# PDM_no_main_relay.net
KiCad netlist of a schematic drawn in EAGLE
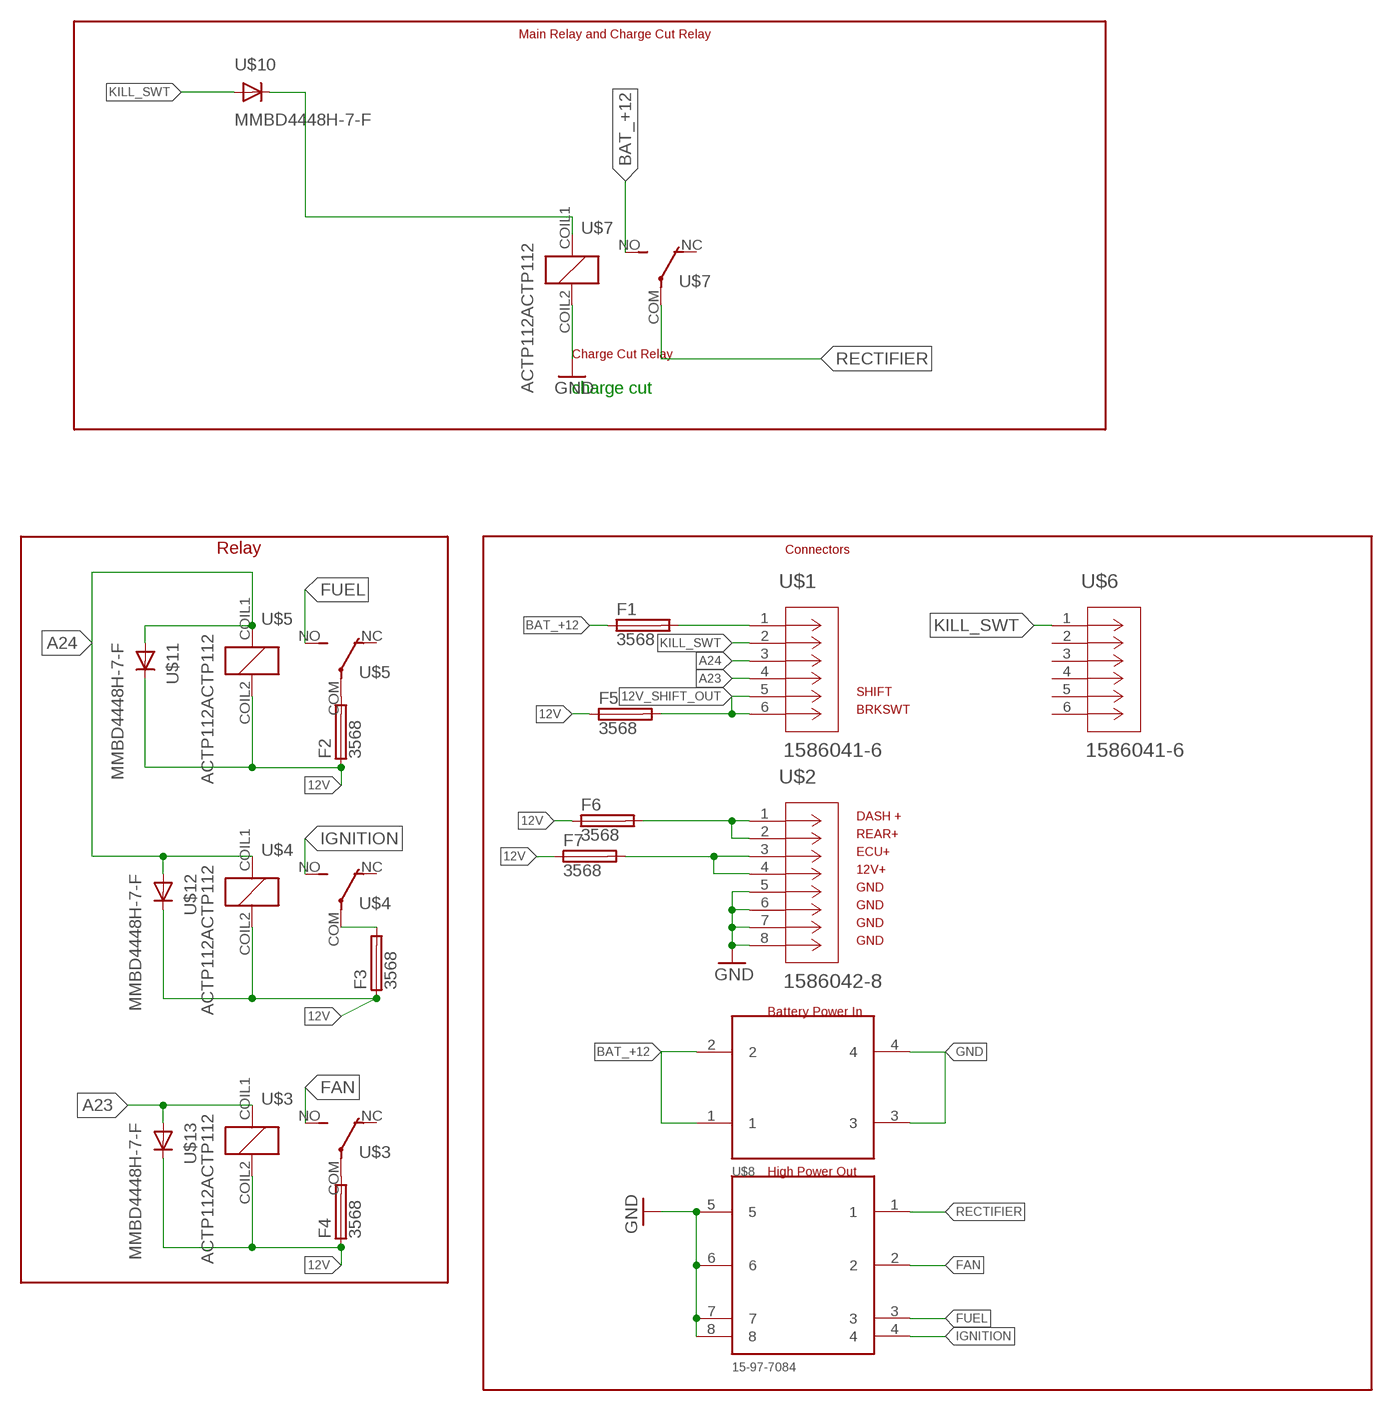
[diagram p0: schematic, sheet 1]

(export (version "E")
  (design (tool "Eeschema 10.0.6"))
  (components
    (comp (ref "F1")
      (value "3568")
      (footprint "eagle-import:3568")
      (libsource (lib "eagle-import") (part "3568"))
    )
    (comp (ref "F2")
      (value "3568")
      (footprint "eagle-import:3568")
      (libsource (lib "eagle-import") (part "3568"))
    )
    (comp (ref "F3")
      (value "3568")
      (footprint "eagle-import:3568")
      (libsource (lib "eagle-import") (part "3568"))
    )
    (comp (ref "F4")
      (value "3568")
      (footprint "eagle-import:3568")
      (libsource (lib "eagle-import") (part "3568"))
    )
    (comp (ref "F5")
      (value "3568")
      (footprint "eagle-import:3568")
      (libsource (lib "eagle-import") (part "3568"))
    )
    (comp (ref "F6")
      (value "3568")
      (footprint "eagle-import:3568")
      (libsource (lib "eagle-import") (part "3568"))
    )
    (comp (ref "F7")
      (value "3568")
      (footprint "eagle-import:3568")
      (libsource (lib "eagle-import") (part "3568"))
    )
    (comp (ref "U$1")
      (value "1586041-6")
      (footprint "eagle-import:1586041-6")
      (libsource (lib "eagle-import") (part "1586041-6"))
    )
    (comp (ref "U$2")
      (value "1586042-8")
      (footprint "eagle-import:1586042-8")
      (libsource (lib "eagle-import") (part "1586042-8"))
    )
    (comp (ref "U$3")
      (value "ACTP112ACTP112")
      (footprint "eagle-import:ACTP112")
      (libsource (lib "eagle-import") (part "ACTP112ACTP112"))
    )
    (comp (ref "U$4")
      (value "ACTP112ACTP112")
      (footprint "eagle-import:ACTP112")
      (libsource (lib "eagle-import") (part "ACTP112ACTP112"))
    )
    (comp (ref "U$5")
      (value "ACTP112ACTP112")
      (footprint "eagle-import:ACTP112")
      (libsource (lib "eagle-import") (part "ACTP112ACTP112"))
    )
    (comp (ref "U$6")
      (value "1586041-6")
      (footprint "eagle-import:1586041-6")
      (libsource (lib "eagle-import") (part "1586041-6"))
    )
    (comp (ref "U$7")
      (value "ACTP112ACTP112")
      (footprint "eagle-import:ACTP112")
      (libsource (lib "eagle-import") (part "ACTP112ACTP112"))
    )
    (comp (ref "U$8")
      (value "15-97-7084")
      (footprint "eagle-import:15-97-7084")
      (libsource (lib "eagle-import") (part "15-97-7084"))
    )
    (comp (ref "U$9")
      (value "15-97-8043")
      (footprint "eagle-import:15-97-8043")
      (libsource (lib "eagle-import") (part "15-97-8043"))
    )
    (comp (ref "U$10")
      (value "MMBD4448H-7-F")
      (footprint "eagle-import:SOT23-3")
      (libsource (lib "eagle-import") (part "MMBD4448H-7-F"))
    )
    (comp (ref "U$11")
      (value "MMBD4448H-7-F")
      (footprint "eagle-import:SOT23-3")
      (libsource (lib "eagle-import") (part "MMBD4448H-7-F"))
    )
    (comp (ref "U$12")
      (value "MMBD4448H-7-F")
      (footprint "eagle-import:SOT23-3")
      (libsource (lib "eagle-import") (part "MMBD4448H-7-F"))
    )
    (comp (ref "U$13")
      (value "MMBD4448H-7-F")
      (footprint "eagle-import:SOT23-3")
      (libsource (lib "eagle-import") (part "MMBD4448H-7-F"))
    )
  )
  (nets
    (net (code "1") (name "12V") (class "Default")
      (node (ref "F2") (pin "1") (pinfunction "1_1") (pintype "passive"))
      (node (ref "F2") (pin "2") (pinfunction "1_2") (pintype "passive"))
      (node (ref "F3") (pin "1") (pinfunction "1_1") (pintype "passive"))
      (node (ref "F3") (pin "2") (pinfunction "1_2") (pintype "passive"))
      (node (ref "F4") (pin "1") (pinfunction "1_1") (pintype "passive"))
      (node (ref "F4") (pin "2") (pinfunction "1_2") (pintype "passive"))
      (node (ref "F5") (pin "1") (pinfunction "1_1") (pintype "passive"))
      (node (ref "F5") (pin "2") (pinfunction "1_2") (pintype "passive"))
      (node (ref "F6") (pin "1") (pinfunction "1_1") (pintype "passive"))
      (node (ref "F6") (pin "2") (pinfunction "1_2") (pintype "passive"))
      (node (ref "F7") (pin "1") (pinfunction "1_1") (pintype "passive"))
      (node (ref "F7") (pin "2") (pinfunction "1_2") (pintype "passive"))
      (node (ref "U$11") (pin "3") (pinfunction "C_3") (pintype "passive"))
      (node (ref "U$12") (pin "3") (pinfunction "C_3") (pintype "passive"))
      (node (ref "U$13") (pin "3") (pinfunction "C_3") (pintype "passive"))
      (node (ref "U$3") (pin "COIL2") (pinfunction "COIL2_COIL2") (pintype "passive"))
      (node (ref "U$4") (pin "COIL2") (pinfunction "COIL2_COIL2") (pintype "passive"))
      (node (ref "U$5") (pin "COIL2") (pinfunction "COIL2_COIL2") (pintype "passive"))
    )
    (net (code "2") (name "12V_SHIFT_OUT") (class "Default")
      (node (ref "F5") (pin "3") (pinfunction "2_3") (pintype "passive"))
      (node (ref "F5") (pin "4") (pinfunction "2_4") (pintype "passive"))
      (node (ref "U$1") (pin "5") (pinfunction "5_5") (pintype "passive"))
      (node (ref "U$1") (pin "6") (pinfunction "6_6") (pintype "passive"))
    )
    (net (code "3") (name "A23") (class "Default")
      (node (ref "U$1") (pin "4") (pinfunction "4_4") (pintype "passive"))
      (node (ref "U$13") (pin "1") (pinfunction "A_1") (pintype "passive"))
      (node (ref "U$3") (pin "COIL1") (pinfunction "COIL1_COIL1") (pintype "passive"))
    )
    (net (code "4") (name "A24") (class "Default")
      (node (ref "U$1") (pin "3") (pinfunction "3_3") (pintype "passive"))
      (node (ref "U$11") (pin "1") (pinfunction "A_1") (pintype "passive"))
      (node (ref "U$12") (pin "1") (pinfunction "A_1") (pintype "passive"))
      (node (ref "U$4") (pin "COIL1") (pinfunction "COIL1_COIL1") (pintype "passive"))
      (node (ref "U$5") (pin "COIL1") (pinfunction "COIL1_COIL1") (pintype "passive"))
    )
    (net (code "5") (name "BAT_+12") (class "Default")
      (node (ref "F1") (pin "1") (pinfunction "1_1") (pintype "passive"))
      (node (ref "F1") (pin "2") (pinfunction "1_2") (pintype "passive"))
      (node (ref "U$7") (pin "NO") (pinfunction "NO_NO") (pintype "passive"))
      (node (ref "U$9") (pin "1") (pinfunction "1_1") (pintype "bidirectional"))
      (node (ref "U$9") (pin "2") (pinfunction "2_2") (pintype "bidirectional"))
    )
    (net (code "6") (name "FAN") (class "Default")
      (node (ref "U$3") (pin "NO") (pinfunction "NO_NO") (pintype "passive"))
      (node (ref "U$8") (pin "2") (pinfunction "2_2") (pintype "bidirectional"))
    )
    (net (code "7") (name "FUEL") (class "Default")
      (node (ref "U$5") (pin "NO") (pinfunction "NO_NO") (pintype "passive"))
      (node (ref "U$8") (pin "3") (pinfunction "3_3") (pintype "bidirectional"))
    )
    (net (code "8") (name "GND") (class "Default")
      (node (ref "U$2") (pin "5") (pinfunction "5_5") (pintype "passive"))
      (node (ref "U$2") (pin "6") (pinfunction "6_6") (pintype "passive"))
      (node (ref "U$2") (pin "7") (pinfunction "7_7") (pintype "passive"))
      (node (ref "U$2") (pin "8") (pinfunction "8_8") (pintype "passive"))
      (node (ref "U$7") (pin "COIL2") (pinfunction "COIL2_COIL2") (pintype "passive"))
      (node (ref "U$8") (pin "5") (pinfunction "5_5") (pintype "bidirectional"))
      (node (ref "U$8") (pin "6") (pinfunction "6_6") (pintype "bidirectional"))
      (node (ref "U$8") (pin "7") (pinfunction "7_7") (pintype "bidirectional"))
      (node (ref "U$8") (pin "8") (pinfunction "8_8") (pintype "bidirectional"))
      (node (ref "U$9") (pin "3") (pinfunction "3_3") (pintype "bidirectional"))
      (node (ref "U$9") (pin "4") (pinfunction "4_4") (pintype "bidirectional"))
    )
    (net (code "9") (name "IGNITION") (class "Default")
      (node (ref "U$4") (pin "NO") (pinfunction "NO_NO") (pintype "passive"))
      (node (ref "U$8") (pin "4") (pinfunction "4_4") (pintype "bidirectional"))
    )
    (net (code "10") (name "KILL_SWT") (class "Default")
      (node (ref "U$1") (pin "2") (pinfunction "2_2") (pintype "passive"))
      (node (ref "U$10") (pin "1") (pinfunction "A_1") (pintype "passive"))
      (node (ref "U$6") (pin "1") (pinfunction "1_1") (pintype "passive"))
    )
    (net (code "11") (name "Net-(F1-2-Pad3)") (class "Default")
      (node (ref "F1") (pin "3") (pinfunction "2_3") (pintype "passive"))
      (node (ref "F1") (pin "4") (pinfunction "2_4") (pintype "passive"))
      (node (ref "U$1") (pin "1") (pinfunction "1_1") (pintype "passive"))
    )
    (net (code "12") (name "Net-(F2-2-Pad3)") (class "Default")
      (node (ref "F2") (pin "3") (pinfunction "2_3") (pintype "passive"))
      (node (ref "F2") (pin "4") (pinfunction "2_4") (pintype "passive"))
      (node (ref "U$5") (pin "COM") (pinfunction "COM_COM") (pintype "passive"))
    )
    (net (code "13") (name "Net-(F3-2-Pad3)") (class "Default")
      (node (ref "F3") (pin "3") (pinfunction "2_3") (pintype "passive"))
      (node (ref "F3") (pin "4") (pinfunction "2_4") (pintype "passive"))
      (node (ref "U$4") (pin "COM") (pinfunction "COM_COM") (pintype "passive"))
    )
    (net (code "14") (name "Net-(F4-2-Pad3)") (class "Default")
      (node (ref "F4") (pin "3") (pinfunction "2_3") (pintype "passive"))
      (node (ref "F4") (pin "4") (pinfunction "2_4") (pintype "passive"))
      (node (ref "U$3") (pin "COM") (pinfunction "COM_COM") (pintype "passive"))
    )
    (net (code "15") (name "Net-(F6-2-Pad3)") (class "Default")
      (node (ref "F6") (pin "3") (pinfunction "2_3") (pintype "passive"))
      (node (ref "F6") (pin "4") (pinfunction "2_4") (pintype "passive"))
      (node (ref "U$2") (pin "1") (pinfunction "1_1") (pintype "passive"))
      (node (ref "U$2") (pin "2") (pinfunction "2_2") (pintype "passive"))
    )
    (net (code "16") (name "Net-(F7-2-Pad3)") (class "Default")
      (node (ref "F7") (pin "3") (pinfunction "2_3") (pintype "passive"))
      (node (ref "F7") (pin "4") (pinfunction "2_4") (pintype "passive"))
      (node (ref "U$2") (pin "3") (pinfunction "3_3") (pintype "passive"))
      (node (ref "U$2") (pin "4") (pinfunction "4_4") (pintype "passive"))
    )
    (net (code "17") (name "Net-(U$10-C)") (class "Default")
      (node (ref "U$10") (pin "3") (pinfunction "C_3") (pintype "passive"))
      (node (ref "U$7") (pin "COIL1") (pinfunction "COIL1_COIL1") (pintype "passive"))
    )
    (net (code "18") (name "RECTIFIER") (class "Default")
      (node (ref "U$7") (pin "COM") (pinfunction "COM_COM") (pintype "passive"))
      (node (ref "U$8") (pin "1") (pinfunction "1_1") (pintype "bidirectional"))
    )
    (net (code "19") (name "unconnected-(U$3-PadNC)") (class "Default")
      (node (ref "U$3") (pin "NC") (pinfunction "NC_NC") (pintype "passive"))
    )
    (net (code "20") (name "unconnected-(U$4-PadNC)") (class "Default")
      (node (ref "U$4") (pin "NC") (pinfunction "NC_NC") (pintype "passive"))
    )
    (net (code "21") (name "unconnected-(U$5-PadNC)") (class "Default")
      (node (ref "U$5") (pin "NC") (pinfunction "NC_NC") (pintype "passive"))
    )
    (net (code "22") (name "unconnected-(U$6-Pad2)") (class "Default")
      (node (ref "U$6") (pin "2") (pinfunction "2_2") (pintype "passive"))
    )
    (net (code "23") (name "unconnected-(U$6-Pad3)") (class "Default")
      (node (ref "U$6") (pin "3") (pinfunction "3_3") (pintype "passive"))
    )
    (net (code "24") (name "unconnected-(U$6-Pad4)") (class "Default")
      (node (ref "U$6") (pin "4") (pinfunction "4_4") (pintype "passive"))
    )
    (net (code "25") (name "unconnected-(U$6-Pad5)") (class "Default")
      (node (ref "U$6") (pin "5") (pinfunction "5_5") (pintype "passive"))
    )
    (net (code "26") (name "unconnected-(U$6-Pad6)") (class "Default")
      (node (ref "U$6") (pin "6") (pinfunction "6_6") (pintype "passive"))
    )
    (net (code "27") (name "unconnected-(U$7-PadNC)") (class "Default")
      (node (ref "U$7") (pin "NC") (pinfunction "NC_NC") (pintype "passive"))
    )
  )
)
